# KickerBoard6A.net
KiCad netlist of a schematic drawn in EAGLE
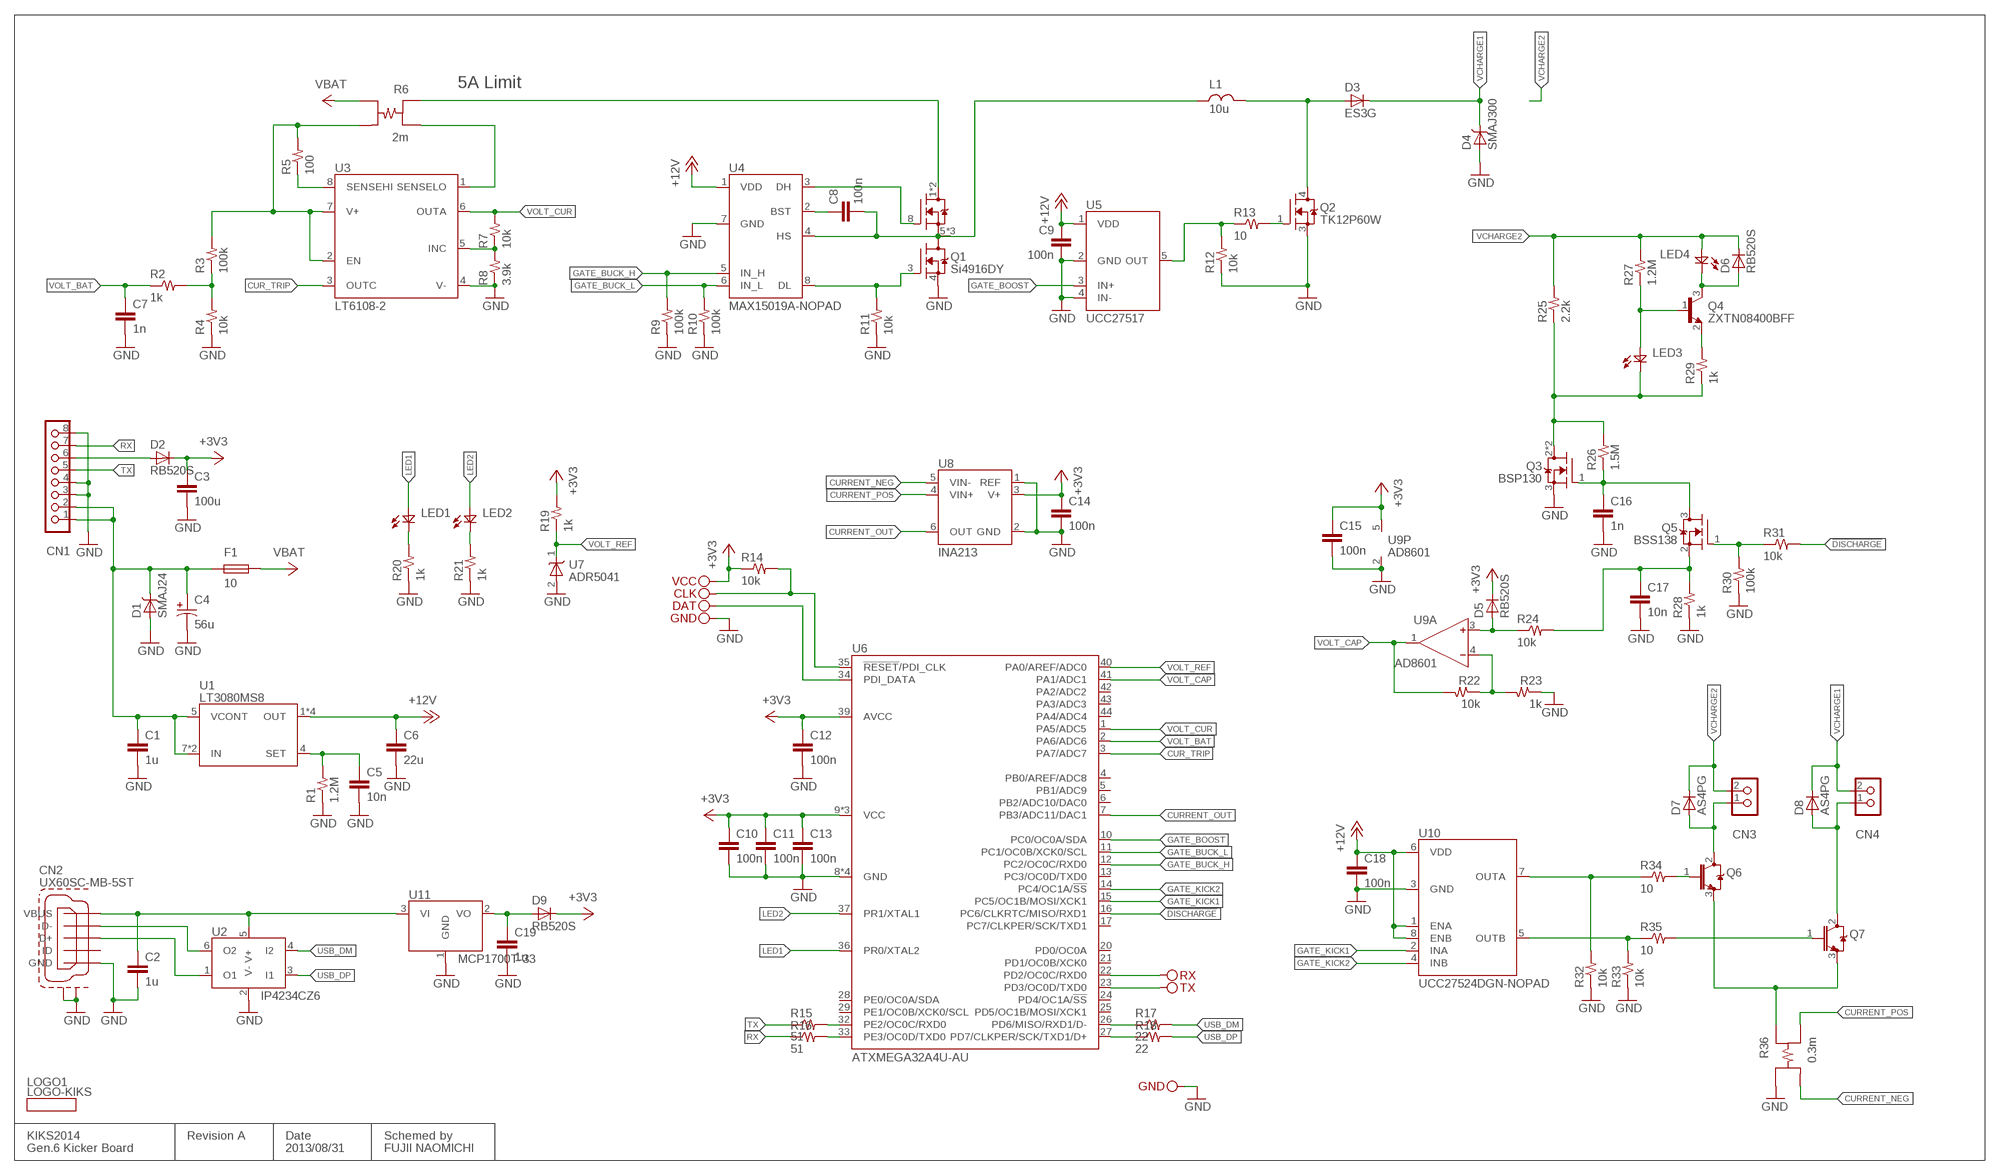
[diagram p0: schematic, sheet 1]

(export (version "E")
  (design (tool "Eeschema 10.0.6"))
  (components
    (comp (ref "C1")
      (value "1u")
      (footprint "eagle-import:1608")
      (libsource (lib "eagle-import") (part "C1608"))
    )
    (comp (ref "C2")
      (value "1u")
      (footprint "eagle-import:1005")
      (libsource (lib "eagle-import") (part "C1005"))
    )
    (comp (ref "C3")
      (value "100u")
      (footprint "eagle-import:3225")
      (libsource (lib "eagle-import") (part "C3225"))
    )
    (comp (ref "C4")
      (value "56u")
      (footprint "eagle-import:ES-6.3")
      (libsource (lib "eagle-import") (part "CPOLS-6.3"))
    )
    (comp (ref "C5")
      (value "10n")
      (footprint "eagle-import:1005")
      (libsource (lib "eagle-import") (part "C1005"))
    )
    (comp (ref "C6")
      (value "22u")
      (footprint "eagle-import:3216")
      (libsource (lib "eagle-import") (part "C3216"))
    )
    (comp (ref "C7")
      (value "1n")
      (footprint "eagle-import:1005")
      (libsource (lib "eagle-import") (part "C1005"))
    )
    (comp (ref "C8")
      (value "100n")
      (footprint "eagle-import:1608")
      (libsource (lib "eagle-import") (part "C1608"))
    )
    (comp (ref "C9")
      (value "100n")
      (footprint "eagle-import:1608")
      (libsource (lib "eagle-import") (part "C1608"))
    )
    (comp (ref "C10")
      (value "100n")
      (footprint "eagle-import:1005")
      (libsource (lib "eagle-import") (part "C1005"))
    )
    (comp (ref "C11")
      (value "100n")
      (footprint "eagle-import:1005")
      (libsource (lib "eagle-import") (part "C1005"))
    )
    (comp (ref "C12")
      (value "100n")
      (footprint "eagle-import:1005")
      (libsource (lib "eagle-import") (part "C1005"))
    )
    (comp (ref "C13")
      (value "100n")
      (footprint "eagle-import:1005")
      (libsource (lib "eagle-import") (part "C1005"))
    )
    (comp (ref "C14")
      (value "100n")
      (footprint "eagle-import:1005")
      (libsource (lib "eagle-import") (part "C1005"))
    )
    (comp (ref "C15")
      (value "100n")
      (footprint "eagle-import:1005")
      (libsource (lib "eagle-import") (part "C1005"))
    )
    (comp (ref "C16")
      (value "1n")
      (footprint "eagle-import:1005")
      (libsource (lib "eagle-import") (part "C1005"))
    )
    (comp (ref "C17")
      (value "10n")
      (footprint "eagle-import:1005")
      (libsource (lib "eagle-import") (part "C1005"))
    )
    (comp (ref "C18")
      (value "100n")
      (footprint "eagle-import:1608")
      (libsource (lib "eagle-import") (part "C1608"))
    )
    (comp (ref "C19")
      (value "1u")
      (footprint "eagle-import:1005")
      (libsource (lib "eagle-import") (part "C1005"))
    )
    (comp (ref "CN1")
      (value "43650-0800")
      (footprint "eagle-import:43650-0800")
      (libsource (lib "eagle-import") (part "43650-0800"))
    )
    (comp (ref "CN2")
      (value "UX60SC-MB-5ST")
      (footprint "eagle-import:UX60SC-MB-5ST")
      (libsource (lib "eagle-import") (part "UX60SC-MB-5ST"))
    )
    (comp (ref "CN3")
      (value "5569-02A2")
      (footprint "eagle-import:5569-02A2")
      (libsource (lib "eagle-import") (part "5569-02A2"))
    )
    (comp (ref "CN4")
      (value "5569-02A2")
      (footprint "eagle-import:5569-02A2")
      (libsource (lib "eagle-import") (part "5569-02A2"))
    )
    (comp (ref "D1")
      (value "SMAJ24")
      (footprint "eagle-import:DO-214AC")
      (libsource (lib "eagle-import") (part "ZENER-DO-214AC"))
    )
    (comp (ref "D2")
      (value "RB520S")
      (footprint "eagle-import:1608")
      (libsource (lib "eagle-import") (part "DIODE-1608"))
    )
    (comp (ref "D3")
      (value "ES3G")
      (footprint "eagle-import:DO-214AB")
      (libsource (lib "eagle-import") (part "DIODE-DO-214AB"))
    )
    (comp (ref "D4")
      (value "SMAJ300")
      (footprint "eagle-import:DO-214AC")
      (libsource (lib "eagle-import") (part "ZENER-DO-214AC"))
    )
    (comp (ref "D5")
      (value "RB520S")
      (footprint "eagle-import:1608")
      (libsource (lib "eagle-import") (part "DIODE-1608"))
    )
    (comp (ref "D6")
      (value "RB520S")
      (footprint "eagle-import:1608")
      (libsource (lib "eagle-import") (part "DIODE-1608"))
    )
    (comp (ref "D7")
      (value "AS4PG")
      (footprint "eagle-import:SMPC")
      (libsource (lib "eagle-import") (part "DIODE-SMPC"))
    )
    (comp (ref "D8")
      (value "AS4PG")
      (footprint "eagle-import:SMPC")
      (libsource (lib "eagle-import") (part "DIODE-SMPC"))
    )
    (comp (ref "D9")
      (value "RB520S")
      (footprint "eagle-import:1608")
      (libsource (lib "eagle-import") (part "DIODE-1608"))
    )
    (comp (ref "F1")
      (value "10")
      (footprint "eagle-import:3216")
      (libsource (lib "eagle-import") (part "F3216"))
    )
    (comp (ref "L1")
      (value "10u")
      (footprint "eagle-import:L8682")
      (libsource (lib "eagle-import") (part "L8682"))
    )
    (comp (ref "LED1")
      (value "LED1611R")
      (footprint "eagle-import:1611")
      (libsource (lib "eagle-import") (part "LED1611R"))
    )
    (comp (ref "LED2")
      (value "LED1611R")
      (footprint "eagle-import:1611")
      (libsource (lib "eagle-import") (part "LED1611R"))
    )
    (comp (ref "LED3")
      (value "LED1608")
      (footprint "eagle-import:1608")
      (libsource (lib "eagle-import") (part "LED1608"))
    )
    (comp (ref "LED4")
      (value "LED1608")
      (footprint "eagle-import:1608")
      (libsource (lib "eagle-import") (part "LED1608"))
    )
    (comp (ref "LOGO1")
      (value "LOGO-KIKS")
      (footprint "eagle-import:LOGO-KIKS")
      (libsource (lib "eagle-import") (part "LOGO-KIKS"))
    )
    (comp (ref "P1")
      (value "VCC")
      (footprint "eagle-import:PAD")
      (libsource (lib "eagle-import") (part "PAD"))
    )
    (comp (ref "P2")
      (value "CLK")
      (footprint "eagle-import:PAD")
      (libsource (lib "eagle-import") (part "PAD"))
    )
    (comp (ref "P3")
      (value "DAT")
      (footprint "eagle-import:PAD")
      (libsource (lib "eagle-import") (part "PAD"))
    )
    (comp (ref "P4")
      (value "GND")
      (footprint "eagle-import:PAD")
      (libsource (lib "eagle-import") (part "PAD"))
    )
    (comp (ref "P5")
      (value "RX")
      (footprint "eagle-import:PAD")
      (libsource (lib "eagle-import") (part "PAD"))
    )
    (comp (ref "P6")
      (value "TX")
      (footprint "eagle-import:PAD")
      (libsource (lib "eagle-import") (part "PAD"))
    )
    (comp (ref "P7")
      (value "GND")
      (footprint "eagle-import:PAD")
      (libsource (lib "eagle-import") (part "PAD"))
    )
    (comp (ref "Q1")
      (value "Si4916DY")
      (footprint "eagle-import:SOP8")
      (libsource (lib "eagle-import") (part "MOS-2N-BRIDGE-SOP8"))
    )
    (comp (ref "Q2")
      (value "TK12P60W")
      (footprint "eagle-import:DPAK-3")
      (libsource (lib "eagle-import") (part "MOS-N-DPAK"))
    )
    (comp (ref "Q3")
      (value "BSP130")
      (footprint "eagle-import:SOT223")
      (libsource (lib "eagle-import") (part "MOS-N-SOT223"))
    )
    (comp (ref "Q4")
      (value "ZXTN08400BFF")
      (footprint "eagle-import:SOT23-3")
      (libsource (lib "eagle-import") (part "NPN-SOT23"))
    )
    (comp (ref "Q5")
      (value "BSS138")
      (footprint "eagle-import:SOT23-3")
      (libsource (lib "eagle-import") (part "MOS-N-SOT23"))
    )
    (comp (ref "Q6")
      (value "IGBT-1N")
      (footprint "eagle-import:TO-247AD_X1")
      (libsource (lib "eagle-import") (part "IGBT-1N"))
    )
    (comp (ref "Q7")
      (value "IGBT-1N")
      (footprint "eagle-import:TO-247AD_X1")
      (libsource (lib "eagle-import") (part "IGBT-1N"))
    )
    (comp (ref "R1")
      (value "1.2M")
      (footprint "eagle-import:1608")
      (libsource (lib "eagle-import") (part "R1608"))
    )
    (comp (ref "R2")
      (value "1k")
      (footprint "eagle-import:1005")
      (libsource (lib "eagle-import") (part "R1005"))
    )
    (comp (ref "R3")
      (value "100k")
      (footprint "eagle-import:1608")
      (libsource (lib "eagle-import") (part "R1608"))
    )
    (comp (ref "R4")
      (value "10k")
      (footprint "eagle-import:1608")
      (libsource (lib "eagle-import") (part "R1608"))
    )
    (comp (ref "R5")
      (value "100")
      (footprint "eagle-import:1608")
      (libsource (lib "eagle-import") (part "R1608"))
    )
    (comp (ref "R6")
      (value "2m")
      (footprint "eagle-import:FC4L")
      (libsource (lib "eagle-import") (part "FC4L"))
    )
    (comp (ref "R7")
      (value "10k")
      (footprint "eagle-import:1608")
      (libsource (lib "eagle-import") (part "R1608"))
    )
    (comp (ref "R8")
      (value "3.9k")
      (footprint "eagle-import:1608")
      (libsource (lib "eagle-import") (part "R1608"))
    )
    (comp (ref "R9")
      (value "100k")
      (footprint "eagle-import:1005")
      (libsource (lib "eagle-import") (part "R1005"))
    )
    (comp (ref "R10")
      (value "100k")
      (footprint "eagle-import:1005")
      (libsource (lib "eagle-import") (part "R1005"))
    )
    (comp (ref "R11")
      (value "10k")
      (footprint "eagle-import:1005")
      (libsource (lib "eagle-import") (part "R1005"))
    )
    (comp (ref "R12")
      (value "10k")
      (footprint "eagle-import:1005")
      (libsource (lib "eagle-import") (part "R1005"))
    )
    (comp (ref "R13")
      (value "10")
      (footprint "eagle-import:2012")
      (libsource (lib "eagle-import") (part "R2012"))
    )
    (comp (ref "R14")
      (value "10k")
      (footprint "eagle-import:1005")
      (libsource (lib "eagle-import") (part "R1005"))
    )
    (comp (ref "R15")
      (value "51")
      (footprint "eagle-import:1005")
      (libsource (lib "eagle-import") (part "R1005"))
    )
    (comp (ref "R16")
      (value "51")
      (footprint "eagle-import:1005")
      (libsource (lib "eagle-import") (part "R1005"))
    )
    (comp (ref "R17")
      (value "22")
      (footprint "eagle-import:1005")
      (libsource (lib "eagle-import") (part "R1005"))
    )
    (comp (ref "R18")
      (value "22")
      (footprint "eagle-import:1005")
      (libsource (lib "eagle-import") (part "R1005"))
    )
    (comp (ref "R19")
      (value "1k")
      (footprint "eagle-import:1005")
      (libsource (lib "eagle-import") (part "R1005"))
    )
    (comp (ref "R20")
      (value "1k")
      (footprint "eagle-import:1005")
      (libsource (lib "eagle-import") (part "R1005"))
    )
    (comp (ref "R21")
      (value "1k")
      (footprint "eagle-import:1005")
      (libsource (lib "eagle-import") (part "R1005"))
    )
    (comp (ref "R22")
      (value "10k")
      (footprint "eagle-import:1608")
      (libsource (lib "eagle-import") (part "R1608"))
    )
    (comp (ref "R23")
      (value "1k")
      (footprint "eagle-import:1608")
      (libsource (lib "eagle-import") (part "R1608"))
    )
    (comp (ref "R24")
      (value "10k")
      (footprint "eagle-import:1005")
      (libsource (lib "eagle-import") (part "R1005"))
    )
    (comp (ref "R25")
      (value "2.2k")
      (footprint "eagle-import:RIEDON-S-3")
      (libsource (lib "eagle-import") (part "R-S-3"))
    )
    (comp (ref "R26")
      (value "1.5M")
      (footprint "eagle-import:1608")
      (libsource (lib "eagle-import") (part "R1608"))
    )
    (comp (ref "R27")
      (value "1.2M")
      (footprint "eagle-import:1608")
      (libsource (lib "eagle-import") (part "R1608"))
    )
    (comp (ref "R28")
      (value "1k")
      (footprint "eagle-import:1608")
      (libsource (lib "eagle-import") (part "R1608"))
    )
    (comp (ref "R29")
      (value "1k")
      (footprint "eagle-import:1005")
      (libsource (lib "eagle-import") (part "R1005"))
    )
    (comp (ref "R30")
      (value "100k")
      (footprint "eagle-import:1005")
      (libsource (lib "eagle-import") (part "R1005"))
    )
    (comp (ref "R31")
      (value "10k")
      (footprint "eagle-import:1005")
      (libsource (lib "eagle-import") (part "R1005"))
    )
    (comp (ref "R32")
      (value "10k")
      (footprint "eagle-import:1005")
      (libsource (lib "eagle-import") (part "R1005"))
    )
    (comp (ref "R33")
      (value "10k")
      (footprint "eagle-import:1005")
      (libsource (lib "eagle-import") (part "R1005"))
    )
    (comp (ref "R34")
      (value "10")
      (footprint "eagle-import:2012")
      (libsource (lib "eagle-import") (part "R2012"))
    )
    (comp (ref "R35")
      (value "10")
      (footprint "eagle-import:2012")
      (libsource (lib "eagle-import") (part "R2012"))
    )
    (comp (ref "R36")
      (value "0.3m")
      (footprint "eagle-import:WSL4026")
      (libsource (lib "eagle-import") (part "R4-WSL4026"))
    )
    (comp (ref "U1")
      (value "LT3080MS8")
      (footprint "eagle-import:MSOP8-PAD")
      (libsource (lib "eagle-import") (part "LT3080MS8"))
    )
    (comp (ref "U2")
      (value "IP4234CZ6")
      (footprint "eagle-import:SOT23-6")
      (libsource (lib "eagle-import") (part "TPD2S017"))
    )
    (comp (ref "U3")
      (value "LT6108-2")
      (footprint "eagle-import:MSOP8")
      (libsource (lib "eagle-import") (part "LT6108-2"))
    )
    (comp (ref "U4")
      (value "MAX15019A-NOPAD")
      (footprint "eagle-import:SOP8")
      (libsource (lib "eagle-import") (part "MAX1501A-NOPAD9"))
    )
    (comp (ref "U5")
      (value "UCC27517")
      (footprint "eagle-import:SOT23-5")
      (libsource (lib "eagle-import") (part "UCC27517"))
    )
    (comp (ref "U6")
      (value "ATXMEGA32A4U-AU")
      (footprint "eagle-import:QFP44-0.8")
      (libsource (lib "eagle-import") (part "ATXMEGAA4U-AU32"))
    )
    (comp (ref "U7")
      (value "ADR5041")
      (footprint "eagle-import:SC70-3")
      (libsource (lib "eagle-import") (part "ADR5041"))
    )
    (comp (ref "U8")
      (value "INA213")
      (footprint "eagle-import:SC70-6")
      (libsource (lib "eagle-import") (part "INA213"))
    )
    (comp (ref "U9")
      (value "AD8601")
      (footprint "eagle-import:SOT23-5")
      (libsource (lib "eagle-import") (part "SINGLE-OPAMP-ISO-SOT23"))
    )
    (comp (ref "U10")
      (value "UCC27524DGN-NOPAD")
      (footprint "eagle-import:MSOP8")
      (libsource (lib "eagle-import") (part "UCC27524DGN-NOPAD"))
    )
    (comp (ref "U11")
      (value "MCP1700T-33")
      (footprint "eagle-import:SOT23-3")
      (libsource (lib "eagle-import") (part "MCP1700T-33"))
    )
  )
  (nets
    (net (code "1") (name "+3V3") (class "Default")
      (node (ref "C10") (pin "1") (pinfunction "1_1") (pintype "passive"))
      (node (ref "C11") (pin "1") (pinfunction "1_1") (pintype "passive"))
      (node (ref "C12") (pin "1") (pinfunction "1_1") (pintype "passive"))
      (node (ref "C13") (pin "1") (pinfunction "1_1") (pintype "passive"))
      (node (ref "C14") (pin "1") (pinfunction "1_1") (pintype "passive"))
      (node (ref "C15") (pin "1") (pinfunction "1_1") (pintype "passive"))
      (node (ref "C3") (pin "1") (pinfunction "1_1") (pintype "passive"))
      (node (ref "D2") (pin "K") (pinfunction "K_K") (pintype "passive"))
      (node (ref "D5") (pin "K") (pinfunction "K_K") (pintype "passive"))
      (node (ref "D9") (pin "K") (pinfunction "K_K") (pintype "passive"))
      (node (ref "P1") (pin "1") (pinfunction "P$1_1") (pintype "passive"))
      (node (ref "R14") (pin "1") (pinfunction "1_1") (pintype "passive"))
      (node (ref "R19") (pin "2") (pinfunction "2_2") (pintype "passive"))
      (node (ref "U6") (pin "19") (pinfunction "VCC_19") (pintype "bidirectional"))
      (node (ref "U6") (pin "31") (pinfunction "VCC_31") (pintype "bidirectional"))
      (node (ref "U6") (pin "39") (pinfunction "AVCC_39") (pintype "bidirectional"))
      (node (ref "U6") (pin "9") (pinfunction "VCC_9") (pintype "bidirectional"))
      (node (ref "U8") (pin "3") (pinfunction "V+_3") (pintype "input"))
      (node (ref "U9") (pin "5") (pinfunction "V+_5") (pintype "input"))
    )
    (net (code "2") (name "+12V") (class "Default")
      (node (ref "C18") (pin "1") (pinfunction "1_1") (pintype "passive"))
      (node (ref "C6") (pin "1") (pinfunction "1_1") (pintype "passive"))
      (node (ref "C9") (pin "1") (pinfunction "1_1") (pintype "passive"))
      (node (ref "U1") (pin "1") (pinfunction "OUT_1") (pintype "bidirectional"))
      (node (ref "U1") (pin "2") (pinfunction "OUT_2") (pintype "bidirectional"))
      (node (ref "U1") (pin "3") (pinfunction "OUT_3") (pintype "bidirectional"))
      (node (ref "U1") (pin "PAD") (pinfunction "OUT_PAD") (pintype "bidirectional"))
      (node (ref "U10") (pin "1") (pinfunction "ENA_1") (pintype "bidirectional"))
      (node (ref "U10") (pin "6") (pinfunction "VDD_6") (pintype "bidirectional"))
      (node (ref "U10") (pin "8") (pinfunction "ENB_8") (pintype "bidirectional"))
      (node (ref "U4") (pin "1") (pinfunction "VDD_1") (pintype "input"))
      (node (ref "U5") (pin "1") (pinfunction "VDD_1") (pintype "bidirectional"))
    )
    (net (code "3") (name "/~{DISCHARGE}") (class "Default")
      (node (ref "R31") (pin "2") (pinfunction "2_2") (pintype "passive"))
      (node (ref "U6") (pin "16") (pinfunction "PC6/CLKRTC/MISO/RXD1_16") (pintype "bidirectional"))
    )
    (net (code "4") (name "CURRENT_NEG") (class "Default")
      (node (ref "R36") (pin "I2") (pinfunction "I2_I2") (pintype "passive"))
      (node (ref "U8") (pin "5") (pinfunction "VIN-_5") (pintype "input"))
    )
    (net (code "5") (name "CURRENT_OUT") (class "Default")
      (node (ref "U6") (pin "7") (pinfunction "PB3/ADC11/DAC1_7") (pintype "bidirectional"))
      (node (ref "U8") (pin "6") (pinfunction "OUT_6") (pintype "output"))
    )
    (net (code "6") (name "CURRENT_POS") (class "Default")
      (node (ref "R36") (pin "I1") (pinfunction "I1_I1") (pintype "passive"))
      (node (ref "U8") (pin "4") (pinfunction "VIN+_4") (pintype "input"))
    )
    (net (code "7") (name "CUR_TRIP") (class "Default")
      (node (ref "U3") (pin "3") (pinfunction "OUTC_3") (pintype "bidirectional"))
      (node (ref "U6") (pin "3") (pinfunction "PA7/ADC7_3") (pintype "bidirectional"))
    )
    (net (code "8") (name "GATE_BOOST") (class "Default")
      (node (ref "U5") (pin "3") (pinfunction "IN+_3") (pintype "bidirectional"))
      (node (ref "U6") (pin "10") (pinfunction "PC0/OC0A/SDA_10") (pintype "bidirectional"))
    )
    (net (code "9") (name "GATE_BUCK_H") (class "Default")
      (node (ref "R9") (pin "2") (pinfunction "2_2") (pintype "passive"))
      (node (ref "U4") (pin "5") (pinfunction "IN_H_5") (pintype "input"))
      (node (ref "U6") (pin "12") (pinfunction "PC2/OC0C/RXD0_12") (pintype "bidirectional"))
    )
    (net (code "10") (name "GATE_BUCK_L") (class "Default")
      (node (ref "R10") (pin "2") (pinfunction "2_2") (pintype "passive"))
      (node (ref "U4") (pin "6") (pinfunction "IN_L_6") (pintype "input"))
      (node (ref "U6") (pin "11") (pinfunction "PC1/OC0B/XCK0/SCL_11") (pintype "bidirectional"))
    )
    (net (code "11") (name "GATE_KICK1") (class "Default")
      (node (ref "U10") (pin "2") (pinfunction "INA_2") (pintype "bidirectional"))
      (node (ref "U6") (pin "15") (pinfunction "PC5/OC1B/MOSI/XCK1_15") (pintype "bidirectional"))
    )
    (net (code "12") (name "GATE_KICK2") (class "Default")
      (node (ref "U10") (pin "4") (pinfunction "INB_4") (pintype "bidirectional"))
      (node (ref "U6") (pin "14") (pinfunction "PC4/OC1A/~{SS}_14") (pintype "bidirectional"))
    )
    (net (code "13") (name "GND") (class "Default")
      (node (ref "C1") (pin "2") (pinfunction "2_2") (pintype "passive"))
      (node (ref "C10") (pin "2") (pinfunction "2_2") (pintype "passive"))
      (node (ref "C11") (pin "2") (pinfunction "2_2") (pintype "passive"))
      (node (ref "C12") (pin "2") (pinfunction "2_2") (pintype "passive"))
      (node (ref "C13") (pin "2") (pinfunction "2_2") (pintype "passive"))
      (node (ref "C14") (pin "2") (pinfunction "2_2") (pintype "passive"))
      (node (ref "C15") (pin "2") (pinfunction "2_2") (pintype "passive"))
      (node (ref "C16") (pin "2") (pinfunction "2_2") (pintype "passive"))
      (node (ref "C17") (pin "2") (pinfunction "2_2") (pintype "passive"))
      (node (ref "C18") (pin "2") (pinfunction "2_2") (pintype "passive"))
      (node (ref "C19") (pin "2") (pinfunction "2_2") (pintype "passive"))
      (node (ref "C2") (pin "2") (pinfunction "2_2") (pintype "passive"))
      (node (ref "C3") (pin "2") (pinfunction "2_2") (pintype "passive"))
      (node (ref "C4") (pin "N") (pinfunction "N_N") (pintype "passive"))
      (node (ref "C5") (pin "2") (pinfunction "2_2") (pintype "passive"))
      (node (ref "C6") (pin "2") (pinfunction "2_2") (pintype "passive"))
      (node (ref "C7") (pin "2") (pinfunction "2_2") (pintype "passive"))
      (node (ref "C9") (pin "2") (pinfunction "2_2") (pintype "passive"))
      (node (ref "CN1") (pin "3") (pinfunction "3_3") (pintype "passive"))
      (node (ref "CN1") (pin "4") (pinfunction "4_4") (pintype "passive"))
      (node (ref "CN1") (pin "8") (pinfunction "8_8") (pintype "passive"))
      (node (ref "CN2") (pin "5") (pinfunction "GND_5") (pintype "passive"))
      (node (ref "CN2") (pin "S1") (pinfunction "S1_S1") (pintype "passive"))
      (node (ref "CN2") (pin "S2") (pinfunction "S2_S2") (pintype "passive"))
      (node (ref "D1") (pin "A") (pinfunction "A_A") (pintype "passive"))
      (node (ref "D4") (pin "A") (pinfunction "A_A") (pintype "passive"))
      (node (ref "P4") (pin "1") (pinfunction "P$1_1") (pintype "passive"))
      (node (ref "P7") (pin "1") (pinfunction "P$1_1") (pintype "passive"))
      (node (ref "Q1") (pin "4") (pinfunction "S2_4") (pintype "passive"))
      (node (ref "Q2") (pin "3") (pinfunction "S_3") (pintype "passive"))
      (node (ref "Q3") (pin "3") (pinfunction "S_3") (pintype "passive"))
      (node (ref "R1") (pin "1") (pinfunction "1_1") (pintype "passive"))
      (node (ref "R10") (pin "1") (pinfunction "1_1") (pintype "passive"))
      (node (ref "R11") (pin "1") (pinfunction "1_1") (pintype "passive"))
      (node (ref "R12") (pin "1") (pinfunction "1_1") (pintype "passive"))
      (node (ref "R20") (pin "1") (pinfunction "1_1") (pintype "passive"))
      (node (ref "R21") (pin "1") (pinfunction "1_1") (pintype "passive"))
      (node (ref "R23") (pin "1") (pinfunction "1_1") (pintype "passive"))
      (node (ref "R28") (pin "1") (pinfunction "1_1") (pintype "passive"))
      (node (ref "R30") (pin "1") (pinfunction "1_1") (pintype "passive"))
      (node (ref "R32") (pin "1") (pinfunction "1_1") (pintype "passive"))
      (node (ref "R33") (pin "1") (pinfunction "1_1") (pintype "passive"))
      (node (ref "R36") (pin "V2") (pinfunction "V2_V2") (pintype "passive"))
      (node (ref "R4") (pin "1") (pinfunction "1_1") (pintype "passive"))
      (node (ref "R8") (pin "1") (pinfunction "1_1") (pintype "passive"))
      (node (ref "R9") (pin "1") (pinfunction "1_1") (pintype "passive"))
      (node (ref "U10") (pin "3") (pinfunction "GND_3") (pintype "bidirectional"))
      (node (ref "U11") (pin "1") (pinfunction "GND_1") (pintype "bidirectional"))
      (node (ref "U2") (pin "2") (pinfunction "V-_2") (pintype "bidirectional"))
      (node (ref "U3") (pin "4") (pinfunction "V-_4") (pintype "bidirectional"))
      (node (ref "U4") (pin "7") (pinfunction "GND_7") (pintype "input"))
      (node (ref "U5") (pin "2") (pinfunction "GND_2") (pintype "bidirectional"))
      (node (ref "U5") (pin "4") (pinfunction "IN-_4") (pintype "bidirectional"))
      (node (ref "U6") (pin "18") (pinfunction "GND_18") (pintype "bidirectional"))
      (node (ref "U6") (pin "30") (pinfunction "GND_30") (pintype "bidirectional"))
      (node (ref "U6") (pin "38") (pinfunction "GND_38") (pintype "bidirectional"))
      (node (ref "U6") (pin "8") (pinfunction "GND_8") (pintype "bidirectional"))
      (node (ref "U7") (pin "2") (pinfunction "A_2") (pintype "passive"))
      (node (ref "U8") (pin "1") (pinfunction "REF_1") (pintype "input"))
      (node (ref "U8") (pin "2") (pinfunction "GND_2") (pintype "input"))
      (node (ref "U9") (pin "2") (pinfunction "V-_2") (pintype "input"))
    )
    (net (code "14") (name "LED1") (class "Default")
      (node (ref "LED1") (pin "A") (pinfunction "A_A") (pintype "passive"))
      (node (ref "U6") (pin "36") (pinfunction "PR0/XTAL2_36") (pintype "bidirectional"))
    )
    (net (code "15") (name "LED2") (class "Default")
      (node (ref "LED2") (pin "A") (pinfunction "A_A") (pintype "passive"))
      (node (ref "U6") (pin "37") (pinfunction "PR1/XTAL1_37") (pintype "bidirectional"))
    )
    (net (code "16") (name "Net-(CN1-Pad6)") (class "Default")
      (node (ref "CN1") (pin "6") (pinfunction "6_6") (pintype "passive"))
      (node (ref "D2") (pin "A") (pinfunction "A_A") (pintype "passive"))
    )
    (net (code "17") (name "Net-(CN2-D+)") (class "Default")
      (node (ref "CN2") (pin "3") (pinfunction "D+_3") (pintype "passive"))
      (node (ref "U2") (pin "1") (pinfunction "O1_1") (pintype "bidirectional"))
    )
    (net (code "18") (name "Net-(CN2-D-)") (class "Default")
      (node (ref "CN2") (pin "2") (pinfunction "D-_2") (pintype "passive"))
      (node (ref "U2") (pin "6") (pinfunction "O2_6") (pintype "bidirectional"))
    )
    (net (code "19") (name "Net-(CN2-VBUS)") (class "Default")
      (node (ref "C2") (pin "1") (pinfunction "1_1") (pintype "passive"))
      (node (ref "CN2") (pin "1") (pinfunction "VBUS_1") (pintype "passive"))
      (node (ref "U11") (pin "3") (pinfunction "VI_3") (pintype "bidirectional"))
      (node (ref "U2") (pin "5") (pinfunction "V+_5") (pintype "bidirectional"))
    )
    (net (code "20") (name "Net-(LED1-PadK)") (class "Default")
      (node (ref "LED1") (pin "K") (pinfunction "K_K") (pintype "passive"))
      (node (ref "R20") (pin "2") (pinfunction "2_2") (pintype "passive"))
    )
    (net (code "21") (name "Net-(LED2-PadK)") (class "Default")
      (node (ref "LED2") (pin "K") (pinfunction "K_K") (pintype "passive"))
      (node (ref "R21") (pin "2") (pinfunction "2_2") (pintype "passive"))
    )
    (net (code "22") (name "Net-(LED3-PadK)") (class "Default")
      (node (ref "LED3") (pin "K") (pinfunction "K_K") (pintype "passive"))
      (node (ref "Q3") (pin "2") (pinfunction "D_2") (pintype "passive"))
      (node (ref "Q3") (pin "4") (pinfunction "D_4") (pintype "passive"))
      (node (ref "R25") (pin "1") (pinfunction "1_1") (pintype "passive"))
      (node (ref "R26") (pin "2") (pinfunction "2_2") (pintype "passive"))
      (node (ref "R29") (pin "1") (pinfunction "1_1") (pintype "passive"))
    )
    (net (code "23") (name "Net-(P2-P$1)") (class "Default")
      (node (ref "P2") (pin "1") (pinfunction "P$1_1") (pintype "passive"))
      (node (ref "R14") (pin "2") (pinfunction "2_2") (pintype "passive"))
      (node (ref "U6") (pin "35") (pinfunction "~{RESET}/PDI_CLK_35") (pintype "bidirectional"))
    )
    (net (code "24") (name "Net-(P3-P$1)") (class "Default")
      (node (ref "P3") (pin "1") (pinfunction "P$1_1") (pintype "passive"))
      (node (ref "U6") (pin "34") (pinfunction "PDI_DATA_34") (pintype "bidirectional"))
    )
    (net (code "25") (name "Net-(P5-P$1)") (class "Default")
      (node (ref "P5") (pin "1") (pinfunction "P$1_1") (pintype "passive"))
      (node (ref "U6") (pin "22") (pinfunction "PD2/OC0C/RXD0_22") (pintype "bidirectional"))
    )
    (net (code "26") (name "Net-(P6-P$1)") (class "Default")
      (node (ref "P6") (pin "1") (pinfunction "P$1_1") (pintype "passive"))
      (node (ref "U6") (pin "23") (pinfunction "PD3/OC0D/TXD0_23") (pintype "bidirectional"))
    )
    (net (code "27") (name "Net-(Q1-D1-Pad1)") (class "Default")
      (node (ref "Q1") (pin "1") (pinfunction "D1_1") (pintype "passive"))
      (node (ref "Q1") (pin "2") (pinfunction "D1_2") (pintype "passive"))
      (node (ref "R6") (pin "V1") (pinfunction "V1_V1") (pintype "passive"))
    )
    (net (code "28") (name "Net-(Q1-G1)") (class "Default")
      (node (ref "Q1") (pin "8") (pinfunction "G1_8") (pintype "passive"))
      (node (ref "U4") (pin "3") (pinfunction "DH_3") (pintype "output"))
    )
    (net (code "29") (name "Net-(Q1-G2)") (class "Default")
      (node (ref "Q1") (pin "3") (pinfunction "G2_3") (pintype "passive"))
      (node (ref "R11") (pin "2") (pinfunction "2_2") (pintype "passive"))
      (node (ref "U4") (pin "8") (pinfunction "DL_8") (pintype "output"))
    )
    (net (code "30") (name "Net-(Q2-D)") (class "Default")
      (node (ref "D3") (pin "A") (pinfunction "A_A") (pintype "passive"))
      (node (ref "L1") (pin "2") (pinfunction "2_2") (pintype "passive"))
      (node (ref "Q2") (pin "4") (pinfunction "D_4") (pintype "passive"))
    )
    (net (code "31") (name "Net-(Q2-G)") (class "Default")
      (node (ref "Q2") (pin "1") (pinfunction "G_1") (pintype "passive"))
      (node (ref "R13") (pin "2") (pinfunction "2_2") (pintype "passive"))
    )
    (net (code "32") (name "Net-(Q3-G)") (class "Default")
      (node (ref "C16") (pin "1") (pinfunction "1_1") (pintype "passive"))
      (node (ref "Q3") (pin "1") (pinfunction "G_1") (pintype "passive"))
      (node (ref "Q5") (pin "3") (pinfunction "D_3") (pintype "passive"))
      (node (ref "R26") (pin "1") (pinfunction "1_1") (pintype "passive"))
    )
    (net (code "33") (name "Net-(Q4-B)") (class "Default")
      (node (ref "LED3") (pin "A") (pinfunction "A_A") (pintype "passive"))
      (node (ref "Q4") (pin "1") (pinfunction "B_1") (pintype "passive"))
      (node (ref "R27") (pin "1") (pinfunction "1_1") (pintype "passive"))
    )
    (net (code "34") (name "Net-(Q4-C)") (class "Default")
      (node (ref "D6") (pin "A") (pinfunction "A_A") (pintype "passive"))
      (node (ref "LED4") (pin "K") (pinfunction "K_K") (pintype "passive"))
      (node (ref "Q4") (pin "3") (pinfunction "C_3") (pintype "passive"))
    )
    (net (code "35") (name "Net-(Q4-E)") (class "Default")
      (node (ref "Q4") (pin "2") (pinfunction "E_2") (pintype "passive"))
      (node (ref "R29") (pin "2") (pinfunction "2_2") (pintype "passive"))
    )
    (net (code "36") (name "Net-(Q5-G)") (class "Default")
      (node (ref "Q5") (pin "1") (pinfunction "G_1") (pintype "passive"))
      (node (ref "R30") (pin "2") (pinfunction "2_2") (pintype "passive"))
      (node (ref "R31") (pin "1") (pinfunction "1_1") (pintype "passive"))
    )
    (net (code "37") (name "Net-(Q5-S)") (class "Default")
      (node (ref "C17") (pin "1") (pinfunction "1_1") (pintype "passive"))
      (node (ref "Q5") (pin "2") (pinfunction "S_2") (pintype "passive"))
      (node (ref "R24") (pin "2") (pinfunction "2_2") (pintype "passive"))
      (node (ref "R28") (pin "2") (pinfunction "2_2") (pintype "passive"))
    )
    (net (code "38") (name "Net-(Q6-C)") (class "Default")
      (node (ref "CN3") (pin "1") (pinfunction "1_1") (pintype "passive"))
      (node (ref "D7") (pin "1") (pinfunction "A_1") (pintype "passive"))
      (node (ref "D7") (pin "2") (pinfunction "A_2") (pintype "passive"))
      (node (ref "Q6") (pin "2") (pinfunction "C_2") (pintype "passive"))
    )
    (net (code "39") (name "Net-(Q6-E)") (class "Default")
      (node (ref "Q6") (pin "3") (pinfunction "E_3") (pintype "passive"))
      (node (ref "Q7") (pin "3") (pinfunction "E_3") (pintype "passive"))
      (node (ref "R36") (pin "V1") (pinfunction "V1_V1") (pintype "passive"))
    )
    (net (code "40") (name "Net-(Q6-G)") (class "Default")
      (node (ref "Q6") (pin "1") (pinfunction "G_1") (pintype "passive"))
      (node (ref "R34") (pin "2") (pinfunction "2_2") (pintype "passive"))
    )
    (net (code "41") (name "Net-(Q7-C)") (class "Default")
      (node (ref "CN4") (pin "1") (pinfunction "1_1") (pintype "passive"))
      (node (ref "D8") (pin "1") (pinfunction "A_1") (pintype "passive"))
      (node (ref "D8") (pin "2") (pinfunction "A_2") (pintype "passive"))
      (node (ref "Q7") (pin "2") (pinfunction "C_2") (pintype "passive"))
    )
    (net (code "42") (name "Net-(Q7-G)") (class "Default")
      (node (ref "Q7") (pin "1") (pinfunction "G_1") (pintype "passive"))
      (node (ref "R35") (pin "2") (pinfunction "2_2") (pintype "passive"))
    )
    (net (code "43") (name "Net-(R2-Pad2)") (class "Default")
      (node (ref "R2") (pin "2") (pinfunction "2_2") (pintype "passive"))
      (node (ref "R3") (pin "1") (pinfunction "1_1") (pintype "passive"))
      (node (ref "R4") (pin "2") (pinfunction "2_2") (pintype "passive"))
    )
    (net (code "44") (name "Net-(U1-SET)") (class "Default")
      (node (ref "C5") (pin "1") (pinfunction "1_1") (pintype "passive"))
      (node (ref "R1") (pin "2") (pinfunction "2_2") (pintype "passive"))
      (node (ref "U1") (pin "4") (pinfunction "SET_4") (pintype "bidirectional"))
    )
    (net (code "45") (name "Net-(U1-VCONT)") (class "Default")
      (node (ref "C1") (pin "1") (pinfunction "1_1") (pintype "passive"))
      (node (ref "C4") (pin "P") (pinfunction "P_P") (pintype "passive"))
      (node (ref "CN1") (pin "1") (pinfunction "1_1") (pintype "passive"))
      (node (ref "CN1") (pin "2") (pinfunction "2_2") (pintype "passive"))
      (node (ref "D1") (pin "K") (pinfunction "K_K") (pintype "passive"))
      (node (ref "F1") (pin "1") (pinfunction "1_1") (pintype "passive"))
      (node (ref "U1") (pin "5") (pinfunction "VCONT_5") (pintype "bidirectional"))
      (node (ref "U1") (pin "7") (pinfunction "IN_7") (pintype "bidirectional"))
      (node (ref "U1") (pin "8") (pinfunction "IN_8") (pintype "bidirectional"))
    )
    (net (code "46") (name "Net-(U3-EN)") (class "Default")
      (node (ref "R3") (pin "2") (pinfunction "2_2") (pintype "passive"))
      (node (ref "R5") (pin "2") (pinfunction "2_2") (pintype "passive"))
      (node (ref "R6") (pin "I2") (pinfunction "I2_I2") (pintype "passive"))
      (node (ref "U3") (pin "2") (pinfunction "EN_2") (pintype "bidirectional"))
      (node (ref "U3") (pin "7") (pinfunction "V+_7") (pintype "bidirectional"))
    )
    (net (code "47") (name "Net-(U3-INC)") (class "Default")
      (node (ref "R7") (pin "1") (pinfunction "1_1") (pintype "passive"))
      (node (ref "R8") (pin "2") (pinfunction "2_2") (pintype "passive"))
      (node (ref "U3") (pin "5") (pinfunction "INC_5") (pintype "bidirectional"))
    )
    (net (code "48") (name "Net-(U3-SENSEHI)") (class "Default")
      (node (ref "R5") (pin "1") (pinfunction "1_1") (pintype "passive"))
      (node (ref "U3") (pin "8") (pinfunction "SENSEHI_8") (pintype "bidirectional"))
    )
    (net (code "49") (name "Net-(U3-SENSELO)") (class "Default")
      (node (ref "R6") (pin "I1") (pinfunction "I1_I1") (pintype "passive"))
      (node (ref "U3") (pin "1") (pinfunction "SENSELO_1") (pintype "bidirectional"))
    )
    (net (code "50") (name "Net-(U4-BST)") (class "Default")
      (node (ref "C8") (pin "1") (pinfunction "1_1") (pintype "passive"))
      (node (ref "U4") (pin "2") (pinfunction "BST_2") (pintype "output"))
    )
    (net (code "51") (name "Net-(U4-HS)") (class "Default")
      (node (ref "C8") (pin "2") (pinfunction "2_2") (pintype "passive"))
      (node (ref "L1") (pin "1") (pinfunction "1_1") (pintype "passive"))
      (node (ref "Q1") (pin "5") (pinfunction "S1_D2_5") (pintype "passive"))
      (node (ref "Q1") (pin "6") (pinfunction "S1_D2_6") (pintype "passive"))
      (node (ref "Q1") (pin "7") (pinfunction "S1_D2_7") (pintype "passive"))
      (node (ref "U4") (pin "4") (pinfunction "HS_4") (pintype "input"))
    )
    (net (code "52") (name "Net-(U5-OUT)") (class "Default")
      (node (ref "R12") (pin "2") (pinfunction "2_2") (pintype "passive"))
      (node (ref "R13") (pin "1") (pinfunction "1_1") (pintype "passive"))
      (node (ref "U5") (pin "5") (pinfunction "OUT_5") (pintype "bidirectional"))
    )
    (net (code "53") (name "Net-(U6-PD6{slash}MISO{slash}RXD1{slash}D-)") (class "Default")
      (node (ref "R17") (pin "1") (pinfunction "1_1") (pintype "passive"))
      (node (ref "U6") (pin "26") (pinfunction "PD6/MISO/RXD1/D-_26") (pintype "bidirectional"))
    )
    (net (code "54") (name "Net-(U6-PD7{slash}CLKPER{slash}SCK{slash}TXD1{slash}D+)") (class "Default")
      (node (ref "R18") (pin "1") (pinfunction "1_1") (pintype "passive"))
      (node (ref "U6") (pin "27") (pinfunction "PD7/CLKPER/SCK/TXD1/D+_27") (pintype "bidirectional"))
    )
    (net (code "55") (name "Net-(U6-PE2{slash}OC0C{slash}RXD0)") (class "Default")
      (node (ref "R15") (pin "2") (pinfunction "2_2") (pintype "passive"))
      (node (ref "U6") (pin "32") (pinfunction "PE2/OC0C/RXD0_32") (pintype "bidirectional"))
    )
    (net (code "56") (name "Net-(U6-PE3{slash}OC0D{slash}TXD0)") (class "Default")
      (node (ref "R16") (pin "2") (pinfunction "2_2") (pintype "passive"))
      (node (ref "U6") (pin "33") (pinfunction "PE3/OC0D/TXD0_33") (pintype "bidirectional"))
    )
    (net (code "57") (name "Net-(U9A-IN+)") (class "Default")
      (node (ref "D5") (pin "A") (pinfunction "A_A") (pintype "passive"))
      (node (ref "R24") (pin "1") (pinfunction "1_1") (pintype "passive"))
      (node (ref "U9") (pin "3") (pinfunction "IN+_3") (pintype "input"))
    )
    (net (code "58") (name "Net-(U9A-IN-)") (class "Default")
      (node (ref "R22") (pin "1") (pinfunction "1_1") (pintype "passive"))
      (node (ref "R23") (pin "2") (pinfunction "2_2") (pintype "passive"))
      (node (ref "U9") (pin "4") (pinfunction "IN-_4") (pintype "input"))
    )
    (net (code "59") (name "Net-(U10-OUTA)") (class "Default")
      (node (ref "R32") (pin "2") (pinfunction "2_2") (pintype "passive"))
      (node (ref "R34") (pin "1") (pinfunction "1_1") (pintype "passive"))
      (node (ref "U10") (pin "7") (pinfunction "OUTA_7") (pintype "bidirectional"))
    )
    (net (code "60") (name "Net-(U10-OUTB)") (class "Default")
      (node (ref "R33") (pin "2") (pinfunction "2_2") (pintype "passive"))
      (node (ref "R35") (pin "1") (pinfunction "1_1") (pintype "passive"))
      (node (ref "U10") (pin "5") (pinfunction "OUTB_5") (pintype "bidirectional"))
    )
    (net (code "61") (name "Net-(U11-VO)") (class "Default")
      (node (ref "C19") (pin "1") (pinfunction "1_1") (pintype "passive"))
      (node (ref "D9") (pin "A") (pinfunction "A_A") (pintype "passive"))
      (node (ref "U11") (pin "2") (pinfunction "VO_2") (pintype "bidirectional"))
    )
    (net (code "62") (name "RX") (class "Default")
      (node (ref "CN1") (pin "7") (pinfunction "7_7") (pintype "passive"))
      (node (ref "R16") (pin "1") (pinfunction "1_1") (pintype "passive"))
    )
    (net (code "63") (name "TX") (class "Default")
      (node (ref "CN1") (pin "5") (pinfunction "5_5") (pintype "passive"))
      (node (ref "R15") (pin "1") (pinfunction "1_1") (pintype "passive"))
    )
    (net (code "64") (name "USB_DM") (class "Default")
      (node (ref "R17") (pin "2") (pinfunction "2_2") (pintype "passive"))
      (node (ref "U2") (pin "4") (pinfunction "I2_4") (pintype "bidirectional"))
    )
    (net (code "65") (name "USB_DP") (class "Default")
      (node (ref "R18") (pin "2") (pinfunction "2_2") (pintype "passive"))
      (node (ref "U2") (pin "3") (pinfunction "I1_3") (pintype "bidirectional"))
    )
    (net (code "66") (name "VBAT") (class "Default")
      (node (ref "F1") (pin "2") (pinfunction "2_2") (pintype "passive"))
      (node (ref "R6") (pin "V2") (pinfunction "V2_V2") (pintype "passive"))
    )
    (net (code "67") (name "VCHARGE1") (class "Default")
      (node (ref "CN4") (pin "2") (pinfunction "2_2") (pintype "passive"))
      (node (ref "D3") (pin "K") (pinfunction "K_K") (pintype "passive"))
      (node (ref "D4") (pin "K") (pinfunction "K_K") (pintype "passive"))
      (node (ref "D8") (pin "K") (pinfunction "K_K") (pintype "passive"))
    )
    (net (code "68") (name "VCHARGE2") (class "Default")
      (node (ref "CN3") (pin "2") (pinfunction "2_2") (pintype "passive"))
      (node (ref "D6") (pin "K") (pinfunction "K_K") (pintype "passive"))
      (node (ref "D7") (pin "K") (pinfunction "K_K") (pintype "passive"))
      (node (ref "LED4") (pin "A") (pinfunction "A_A") (pintype "passive"))
      (node (ref "R25") (pin "2") (pinfunction "2_2") (pintype "passive"))
      (node (ref "R27") (pin "2") (pinfunction "2_2") (pintype "passive"))
    )
    (net (code "69") (name "VOLT_BAT") (class "Default")
      (node (ref "C7") (pin "1") (pinfunction "1_1") (pintype "passive"))
      (node (ref "R2") (pin "1") (pinfunction "1_1") (pintype "passive"))
      (node (ref "U6") (pin "2") (pinfunction "PA6/ADC6_2") (pintype "bidirectional"))
    )
    (net (code "70") (name "VOLT_CAP") (class "Default")
      (node (ref "R22") (pin "2") (pinfunction "2_2") (pintype "passive"))
      (node (ref "U6") (pin "41") (pinfunction "PA1/ADC1_41") (pintype "bidirectional"))
      (node (ref "U9") (pin "1") (pinfunction "OUT_1") (pintype "output"))
    )
    (net (code "71") (name "VOLT_CUR") (class "Default")
      (node (ref "R7") (pin "2") (pinfunction "2_2") (pintype "passive"))
      (node (ref "U3") (pin "6") (pinfunction "OUTA_6") (pintype "bidirectional"))
      (node (ref "U6") (pin "1") (pinfunction "PA5/ADC5_1") (pintype "bidirectional"))
    )
    (net (code "72") (name "VOLT_REF") (class "Default")
      (node (ref "R19") (pin "1") (pinfunction "1_1") (pintype "passive"))
      (node (ref "U6") (pin "40") (pinfunction "PA0/AREF/ADC0_40") (pintype "bidirectional"))
      (node (ref "U7") (pin "1") (pinfunction "K_1") (pintype "passive"))
    )
    (net (code "73") (name "unconnected-(CN2-ID-Pad4)") (class "Default")
      (node (ref "CN2") (pin "4") (pinfunction "ID_4") (pintype "passive"))
    )
    (net (code "74") (name "unconnected-(U6-PA2{slash}ADC2-Pad42)") (class "Default")
      (node (ref "U6") (pin "42") (pinfunction "PA2/ADC2_42") (pintype "bidirectional"))
    )
    (net (code "75") (name "unconnected-(U6-PA3{slash}ADC3-Pad43)") (class "Default")
      (node (ref "U6") (pin "43") (pinfunction "PA3/ADC3_43") (pintype "bidirectional"))
    )
    (net (code "76") (name "unconnected-(U6-PA4{slash}ADC4-Pad44)") (class "Default")
      (node (ref "U6") (pin "44") (pinfunction "PA4/ADC4_44") (pintype "bidirectional"))
    )
    (net (code "77") (name "unconnected-(U6-PB0{slash}AREF{slash}ADC8-Pad4)") (class "Default")
      (node (ref "U6") (pin "4") (pinfunction "PB0/AREF/ADC8_4") (pintype "bidirectional"))
    )
    (net (code "78") (name "unconnected-(U6-PB1{slash}ADC9-Pad5)") (class "Default")
      (node (ref "U6") (pin "5") (pinfunction "PB1/ADC9_5") (pintype "bidirectional"))
    )
    (net (code "79") (name "unconnected-(U6-PB2{slash}ADC10{slash}DAC0-Pad6)") (class "Default")
      (node (ref "U6") (pin "6") (pinfunction "PB2/ADC10/DAC0_6") (pintype "bidirectional"))
    )
    (net (code "80") (name "unconnected-(U6-PC3{slash}OC0D{slash}TXD0-Pad13)") (class "Default")
      (node (ref "U6") (pin "13") (pinfunction "PC3/OC0D/TXD0_13") (pintype "bidirectional"))
    )
    (net (code "81") (name "unconnected-(U6-PC7{slash}CLKPER{slash}SCK{slash}TXD1-Pad17)") (class "Default")
      (node (ref "U6") (pin "17") (pinfunction "PC7/CLKPER/SCK/TXD1_17") (pintype "bidirectional"))
    )
    (net (code "82") (name "unconnected-(U6-PD0{slash}OC0A-Pad20)") (class "Default")
      (node (ref "U6") (pin "20") (pinfunction "PD0/OC0A_20") (pintype "bidirectional"))
    )
    (net (code "83") (name "unconnected-(U6-PD1{slash}OC0B{slash}XCK0-Pad21)") (class "Default")
      (node (ref "U6") (pin "21") (pinfunction "PD1/OC0B/XCK0_21") (pintype "bidirectional"))
    )
    (net (code "84") (name "unconnected-(U6-PD4{slash}OC1A{slash}~{SS}-Pad24)") (class "Default")
      (node (ref "U6") (pin "24") (pinfunction "PD4/OC1A/~{SS}_24") (pintype "bidirectional"))
    )
    (net (code "85") (name "unconnected-(U6-PD5{slash}OC1B{slash}MOSI{slash}XCK1-Pad25)") (class "Default")
      (node (ref "U6") (pin "25") (pinfunction "PD5/OC1B/MOSI/XCK1_25") (pintype "bidirectional"))
    )
    (net (code "86") (name "unconnected-(U6-PE0{slash}OC0A{slash}SDA-Pad28)") (class "Default")
      (node (ref "U6") (pin "28") (pinfunction "PE0/OC0A/SDA_28") (pintype "bidirectional"))
    )
    (net (code "87") (name "unconnected-(U6-PE1{slash}OC0B{slash}XCK0{slash}SCL-Pad29)") (class "Default")
      (node (ref "U6") (pin "29") (pinfunction "PE1/OC0B/XCK0/SCL_29") (pintype "bidirectional"))
    )
  )
)
